# ESP12-breakout-pth-rev2.net
KiCad netlist of a schematic drawn in EAGLE
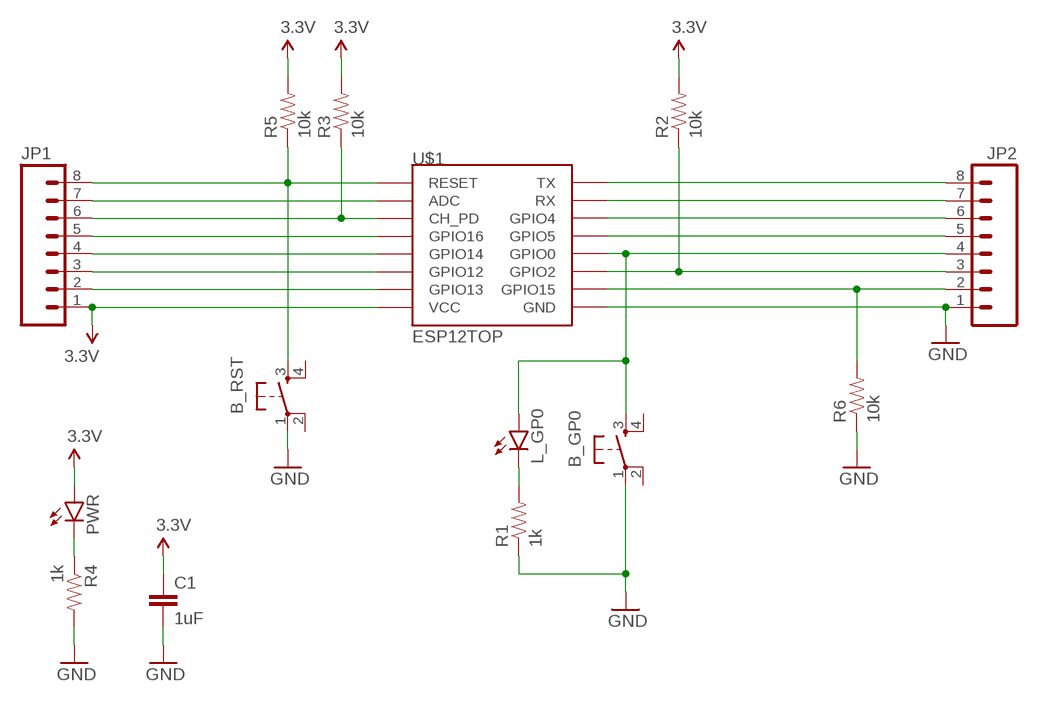
[diagram p0: schematic, sheet 1]

(export (version "E")
  (design (tool "Eeschema 10.0.6"))
  (components
    (comp (ref "B_GP0")
      (value "TAC_SWITCHPTH")
      (footprint "eagle-import:TACTILE-PTH")
      (libsource (lib "eagle-import") (part "TAC_SWITCHPTH"))
    )
    (comp (ref "B_RST")
      (value "TAC_SWITCHPTH")
      (footprint "eagle-import:TACTILE-PTH")
      (libsource (lib "eagle-import") (part "TAC_SWITCHPTH"))
    )
    (comp (ref "C1")
      (value "1uF")
      (footprint "eagle-import:CAP-PTH-SMALL")
      (libsource (lib "eagle-import") (part "CAPPTH"))
    )
    (comp (ref "JP1")
      (value "M08")
      (footprint "eagle-import:1X08_PIN1_NO_SILK")
      (libsource (lib "eagle-import") (part "M08"))
    )
    (comp (ref "JP2")
      (value "M08")
      (footprint "eagle-import:1X08_PIN1_NO_SILK")
      (libsource (lib "eagle-import") (part "M08"))
    )
    (comp (ref "L_GP0")
      (value "LED3MM")
      (footprint "eagle-import:LED3MM")
      (libsource (lib "eagle-import") (part "LED3MM"))
    )
    (comp (ref "PWR")
      (value "LED3MM")
      (footprint "eagle-import:LED3MM")
      (libsource (lib "eagle-import") (part "LED3MM"))
    )
    (comp (ref "R1")
      (value "1k")
      (footprint "eagle-import:1_6W-RES")
      (libsource (lib "eagle-import") (part "RESISTORPTH-1/6W"))
    )
    (comp (ref "R2")
      (value "10k")
      (footprint "eagle-import:1_6W-RES")
      (libsource (lib "eagle-import") (part "RESISTORPTH-1/6W"))
    )
    (comp (ref "R3")
      (value "10k")
      (footprint "eagle-import:1_6W-RES")
      (libsource (lib "eagle-import") (part "RESISTORPTH-1/6W"))
    )
    (comp (ref "R4")
      (value "1k")
      (footprint "eagle-import:1_6W-RES")
      (libsource (lib "eagle-import") (part "RESISTORPTH-1/6W"))
    )
    (comp (ref "R5")
      (value "10k")
      (footprint "eagle-import:1_6W-RES")
      (libsource (lib "eagle-import") (part "RESISTORPTH-1/6W"))
    )
    (comp (ref "R6")
      (value "10k")
      (footprint "eagle-import:1_6W-RES")
      (libsource (lib "eagle-import") (part "RESISTORPTH-1/6W"))
    )
    (comp (ref "U$1")
      (value "ESP12TOP")
      (footprint "eagle-import:ESP12TOP")
      (libsource (lib "eagle-import") (part "ESP12TOP"))
    )
  )
  (nets
    (net (code "1") (name "3.3V") (class "Default")
      (node (ref "C1") (pin "1") (pinfunction "1_1") (pintype "passive"))
      (node (ref "JP1") (pin "1") (pinfunction "1_1") (pintype "passive"))
      (node (ref "PWR") (pin "A") (pinfunction "A_A") (pintype "passive"))
      (node (ref "R2") (pin "2") (pinfunction "2_2") (pintype "passive"))
      (node (ref "R3") (pin "2") (pinfunction "2_2") (pintype "passive"))
      (node (ref "R5") (pin "2") (pinfunction "2_2") (pintype "passive"))
      (node (ref "U$1") (pin "VCC") (pinfunction "VCC_VCC") (pintype "bidirectional"))
    )
    (net (code "2") (name "GND") (class "Default")
      (node (ref "B_GP0") (pin "1") (pinfunction "1_1") (pintype "passive"))
      (node (ref "B_RST") (pin "1") (pinfunction "1_1") (pintype "passive"))
      (node (ref "C1") (pin "2") (pinfunction "2_2") (pintype "passive"))
      (node (ref "JP2") (pin "1") (pinfunction "1_1") (pintype "passive"))
      (node (ref "R1") (pin "1") (pinfunction "1_1") (pintype "passive"))
      (node (ref "R4") (pin "2") (pinfunction "2_2") (pintype "passive"))
      (node (ref "R6") (pin "1") (pinfunction "1_1") (pintype "passive"))
      (node (ref "U$1") (pin "GND") (pinfunction "GND_GND") (pintype "bidirectional"))
    )
    (net (code "3") (name "Net-(B_GP0-Pad3)") (class "Default")
      (node (ref "B_GP0") (pin "3") (pinfunction "3_3") (pintype "passive"))
      (node (ref "JP2") (pin "4") (pinfunction "4_4") (pintype "passive"))
      (node (ref "L_GP0") (pin "A") (pinfunction "A_A") (pintype "passive"))
      (node (ref "U$1") (pin "GPIO0") (pinfunction "GPIO0_GPIO0") (pintype "bidirectional"))
    )
    (net (code "4") (name "Net-(B_RST-Pad3)") (class "Default")
      (node (ref "B_RST") (pin "3") (pinfunction "3_3") (pintype "passive"))
      (node (ref "JP1") (pin "8") (pinfunction "8_8") (pintype "passive"))
      (node (ref "R5") (pin "1") (pinfunction "1_1") (pintype "passive"))
      (node (ref "U$1") (pin "RESET") (pinfunction "RESET_RESET") (pintype "bidirectional"))
    )
    (net (code "5") (name "Net-(JP1-Pad2)") (class "Default")
      (node (ref "JP1") (pin "2") (pinfunction "2_2") (pintype "passive"))
      (node (ref "U$1") (pin "GPIO13") (pinfunction "GPIO13_GPIO13") (pintype "bidirectional"))
    )
    (net (code "6") (name "Net-(JP1-Pad3)") (class "Default")
      (node (ref "JP1") (pin "3") (pinfunction "3_3") (pintype "passive"))
      (node (ref "U$1") (pin "GPIO12") (pinfunction "GPIO12_GPIO12") (pintype "bidirectional"))
    )
    (net (code "7") (name "Net-(JP1-Pad4)") (class "Default")
      (node (ref "JP1") (pin "4") (pinfunction "4_4") (pintype "passive"))
      (node (ref "U$1") (pin "GPIO14") (pinfunction "GPIO14_GPIO14") (pintype "bidirectional"))
    )
    (net (code "8") (name "Net-(JP1-Pad5)") (class "Default")
      (node (ref "JP1") (pin "5") (pinfunction "5_5") (pintype "passive"))
      (node (ref "U$1") (pin "GPIO16") (pinfunction "GPIO16_GPIO16") (pintype "bidirectional"))
    )
    (net (code "9") (name "Net-(JP1-Pad6)") (class "Default")
      (node (ref "JP1") (pin "6") (pinfunction "6_6") (pintype "passive"))
      (node (ref "R3") (pin "1") (pinfunction "1_1") (pintype "passive"))
      (node (ref "U$1") (pin "CH_PD") (pinfunction "CH_PD_CH_PD") (pintype "bidirectional"))
    )
    (net (code "10") (name "Net-(JP1-Pad7)") (class "Default")
      (node (ref "JP1") (pin "7") (pinfunction "7_7") (pintype "passive"))
      (node (ref "U$1") (pin "ADC") (pinfunction "ADC_ADC") (pintype "bidirectional"))
    )
    (net (code "11") (name "Net-(JP2-Pad2)") (class "Default")
      (node (ref "JP2") (pin "2") (pinfunction "2_2") (pintype "passive"))
      (node (ref "R6") (pin "2") (pinfunction "2_2") (pintype "passive"))
      (node (ref "U$1") (pin "GPIO15") (pinfunction "GPIO15_GPIO15") (pintype "bidirectional"))
    )
    (net (code "12") (name "Net-(JP2-Pad3)") (class "Default")
      (node (ref "JP2") (pin "3") (pinfunction "3_3") (pintype "passive"))
      (node (ref "R2") (pin "1") (pinfunction "1_1") (pintype "passive"))
      (node (ref "U$1") (pin "GPIO2") (pinfunction "GPIO2_GPIO2") (pintype "bidirectional"))
    )
    (net (code "13") (name "Net-(JP2-Pad5)") (class "Default")
      (node (ref "JP2") (pin "5") (pinfunction "5_5") (pintype "passive"))
      (node (ref "U$1") (pin "GPIO5") (pinfunction "GPIO5_GPIO5") (pintype "bidirectional"))
    )
    (net (code "14") (name "Net-(JP2-Pad6)") (class "Default")
      (node (ref "JP2") (pin "6") (pinfunction "6_6") (pintype "passive"))
      (node (ref "U$1") (pin "GPIO4") (pinfunction "GPIO4_GPIO4") (pintype "bidirectional"))
    )
    (net (code "15") (name "Net-(L_GP0-C)") (class "Default")
      (node (ref "L_GP0") (pin "K") (pinfunction "C_K") (pintype "passive"))
      (node (ref "R1") (pin "2") (pinfunction "2_2") (pintype "passive"))
    )
    (net (code "16") (name "Net-(PWR-C)") (class "Default")
      (node (ref "PWR") (pin "K") (pinfunction "C_K") (pintype "passive"))
      (node (ref "R4") (pin "1") (pinfunction "1_1") (pintype "passive"))
    )
    (net (code "17") (name "Net-(U$1-RX)") (class "Default")
      (node (ref "JP2") (pin "7") (pinfunction "7_7") (pintype "passive"))
      (node (ref "U$1") (pin "RXD") (pinfunction "RX_RXD") (pintype "bidirectional"))
    )
    (net (code "18") (name "Net-(U$1-TX)") (class "Default")
      (node (ref "JP2") (pin "8") (pinfunction "8_8") (pintype "passive"))
      (node (ref "U$1") (pin "TXD") (pinfunction "TX_TXD") (pintype "bidirectional"))
    )
    (net (code "19") (name "unconnected-(B_GP0-Pad2)") (class "Default")
      (node (ref "B_GP0") (pin "2") (pinfunction "2_2") (pintype "passive"))
    )
    (net (code "20") (name "unconnected-(B_GP0-Pad4)") (class "Default")
      (node (ref "B_GP0") (pin "4") (pinfunction "4_4") (pintype "passive"))
    )
    (net (code "21") (name "unconnected-(B_RST-Pad2)") (class "Default")
      (node (ref "B_RST") (pin "2") (pinfunction "2_2") (pintype "passive"))
    )
    (net (code "22") (name "unconnected-(B_RST-Pad4)") (class "Default")
      (node (ref "B_RST") (pin "4") (pinfunction "4_4") (pintype "passive"))
    )
  )
)
